# JoyCoder.net
KiCad netlist of a schematic drawn in EAGLE
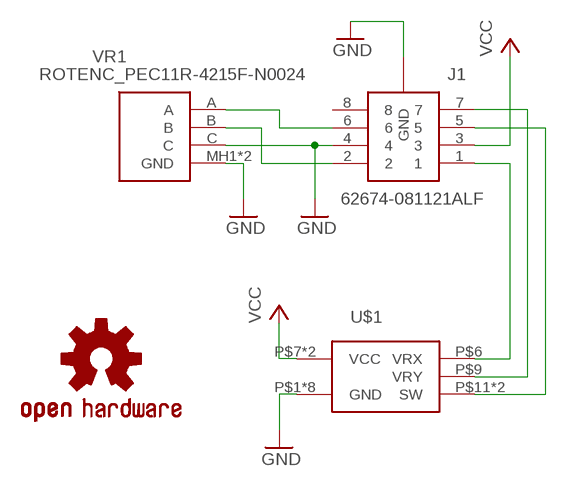
[diagram p0: schematic, sheet 1]

(export (version "E")
  (design (tool "Eeschema 10.0.6"))
  (components
    (comp (ref "J1")
      (value "62674-081121ALF")
      (footprint "eagle-import:FCI_62674-081121ALF")
      (fields
        (field (name "MOUSER_PART_NUMBER") "649-62674-081121ALF")
        (field (name "RS_PART_NUMBER") "6734847")
      )
      (libsource (lib "eagle-import") (part "62674-081121ALF"))
    )
    (comp (ref "LOGO1")
      (value "OSHW-LOGOS")
      (footprint "eagle-import:OSHW-LOGO-S")
      (libsource (lib "eagle-import") (part "OSHW-LOGOS"))
    )
    (comp (ref "U$1")
      (value "JOYSTICK")
      (footprint "eagle-import:JOYSTICK_PS2")
      (libsource (lib "eagle-import") (part "JOYSTICK"))
    )
    (comp (ref "VR1")
      (value "ROTENC_PEC11R-4215F-N0024")
      (footprint "eagle-import:ROTENC_PEC11R-4215F-N0024")
      (fields
        (field (name "MANUFACTURER_PART_NUMBER") "PEC11R-4220F-S0024")
        (field (name "MOUSER_PART_NUMBER") "652-PEC11R-4220F-S24")
        (field (name "RS_PART_NUMBER") "1674659")
      )
      (libsource (lib "eagle-import") (part "ROTENC_PEC11R-4215F-N0024"))
    )
  )
  (nets
    (net (code "1") (name "GND") (class "Default")
      (node (ref "J1") (pin "10") (pinfunction "GND_10") (pintype "bidirectional"))
      (node (ref "J1") (pin "11") (pinfunction "GND_11") (pintype "bidirectional"))
      (node (ref "J1") (pin "12") (pinfunction "GND_12") (pintype "bidirectional"))
      (node (ref "J1") (pin "4") (pinfunction "4_4") (pintype "bidirectional"))
      (node (ref "J1") (pin "9") (pinfunction "GND_9") (pintype "bidirectional"))
      (node (ref "U$1") (pin "P$1") (pinfunction "GND_P$1") (pintype "bidirectional"))
      (node (ref "U$1") (pin "P$13") (pinfunction "GND_P$13") (pintype "bidirectional"))
      (node (ref "U$1") (pin "P$14") (pinfunction "GND_P$14") (pintype "bidirectional"))
      (node (ref "U$1") (pin "P$2") (pinfunction "GND_P$2") (pintype "bidirectional"))
      (node (ref "U$1") (pin "P$3") (pinfunction "GND_P$3") (pintype "bidirectional"))
      (node (ref "U$1") (pin "P$4") (pinfunction "GND_P$4") (pintype "bidirectional"))
      (node (ref "U$1") (pin "P$5") (pinfunction "GND_P$5") (pintype "bidirectional"))
      (node (ref "U$1") (pin "P$8") (pinfunction "GND_P$8") (pintype "bidirectional"))
      (node (ref "VR1") (pin "C") (pinfunction "C_C") (pintype "bidirectional"))
      (node (ref "VR1") (pin "MH1") (pinfunction "GND_MH1") (pintype "bidirectional"))
      (node (ref "VR1") (pin "MH2") (pinfunction "GND_MH2") (pintype "bidirectional"))
    )
    (net (code "2") (name "Net-(J1-Pad2)") (class "Default")
      (node (ref "J1") (pin "2") (pinfunction "2_2") (pintype "bidirectional"))
      (node (ref "VR1") (pin "B") (pinfunction "B_B") (pintype "bidirectional"))
    )
    (net (code "3") (name "Net-(J1-Pad5)") (class "Default")
      (node (ref "J1") (pin "5") (pinfunction "5_5") (pintype "bidirectional"))
      (node (ref "U$1") (pin "P$11") (pinfunction "SW_P$11") (pintype "bidirectional"))
      (node (ref "U$1") (pin "P$12") (pinfunction "SW_P$12") (pintype "bidirectional"))
    )
    (net (code "4") (name "Net-(J1-Pad6)") (class "Default")
      (node (ref "J1") (pin "6") (pinfunction "6_6") (pintype "bidirectional"))
      (node (ref "VR1") (pin "A") (pinfunction "A_A") (pintype "bidirectional"))
    )
    (net (code "5") (name "Net-(U$1-VRX)") (class "Default")
      (node (ref "J1") (pin "1") (pinfunction "1_1") (pintype "bidirectional"))
      (node (ref "U$1") (pin "P$6") (pinfunction "VRX_P$6") (pintype "bidirectional"))
    )
    (net (code "6") (name "Net-(U$1-VRY)") (class "Default")
      (node (ref "J1") (pin "7") (pinfunction "7_7") (pintype "bidirectional"))
      (node (ref "U$1") (pin "P$9") (pinfunction "VRY_P$9") (pintype "bidirectional"))
    )
    (net (code "7") (name "VCC") (class "Default")
      (node (ref "J1") (pin "3") (pinfunction "3_3") (pintype "bidirectional"))
      (node (ref "U$1") (pin "P$10") (pinfunction "VCC_P$10") (pintype "bidirectional"))
      (node (ref "U$1") (pin "P$7") (pinfunction "VCC_P$7") (pintype "bidirectional"))
    )
    (net (code "8") (name "unconnected-(J1-Pad8)") (class "Default")
      (node (ref "J1") (pin "8") (pinfunction "8_8") (pintype "bidirectional"))
    )
  )
)
